# FeatherAB1805-SC.net
KiCad netlist of a schematic drawn in EAGLE
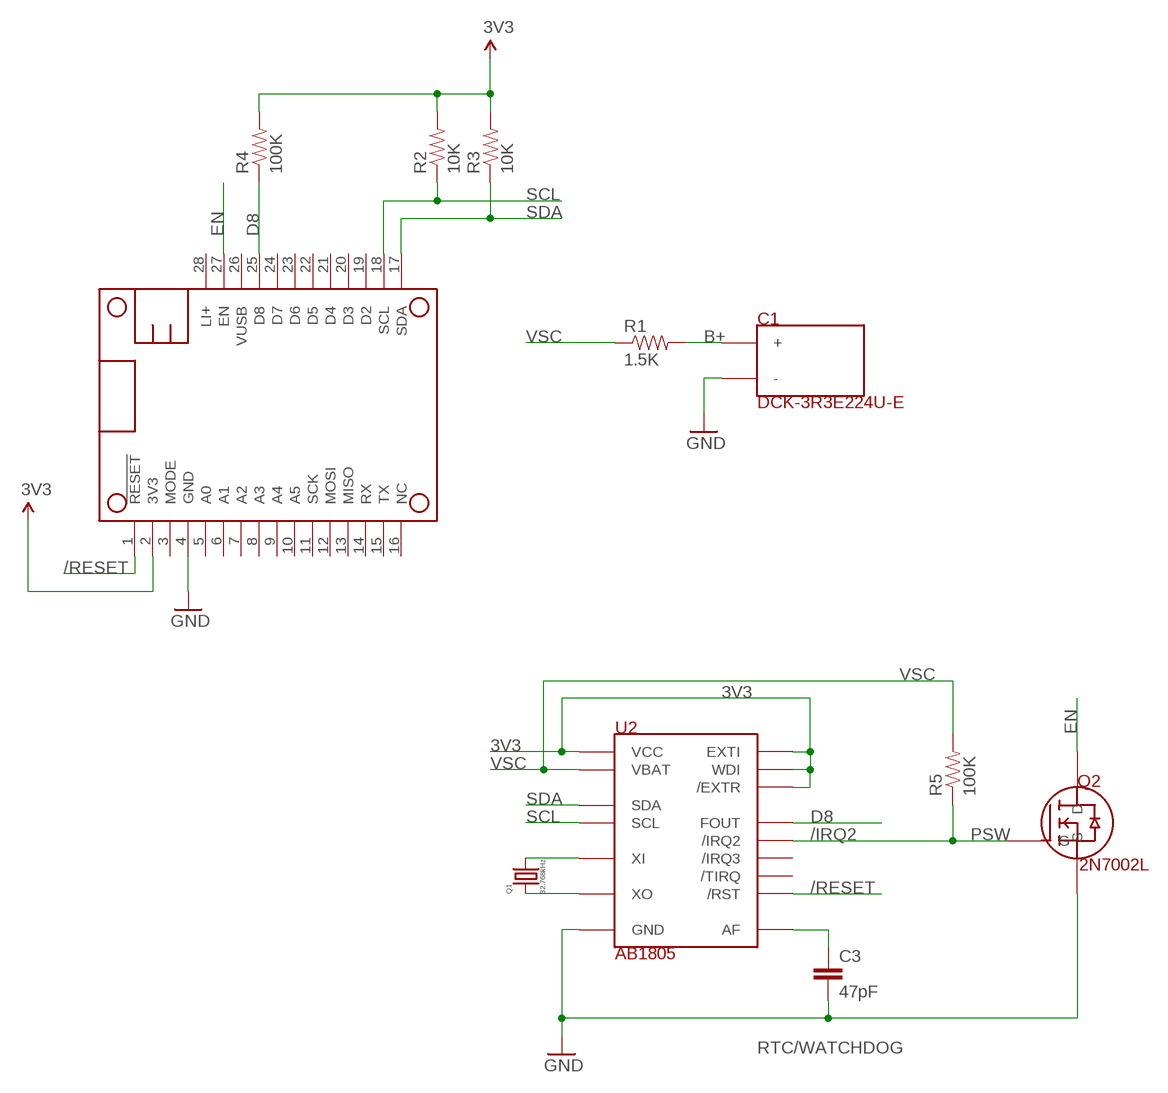
[diagram p0: schematic, sheet 1]

(export (version "E")
  (design (tool "Eeschema 10.0.6"))
  (components
    (comp (ref "C1")
      (value "DCK-3R3E224U-E")
      (footprint "eagle-import:SUPERCAP-DCK-3R3E224U-E")
      (libsource (lib "eagle-import") (part "SUPERCAP-DCK-3R3E224U-E"))
    )
    (comp (ref "C3")
      (value "47pF")
      (footprint "eagle-import:0603-CAP")
      (libsource (lib "eagle-import") (part "CAP-47PF-0603"))
    )
    (comp (ref "MS1")
      (value "FEATHERWING_NODIM")
      (footprint "eagle-import:FEATHERWING_NODIM")
      (libsource (lib "eagle-import") (part "FEATHERWING_NODIM"))
    )
    (comp (ref "Q1")
      (value "32.768kHz")
      (footprint "eagle-import:ABS07-120-CRYSTAL")
      (libsource (lib "eagle-import") (part "ABS07-120-32.768KHZ"))
    )
    (comp (ref "Q2")
      (value "2N7002L")
      (footprint "eagle-import:2N7002L")
      (libsource (lib "eagle-import") (part "2N7002L"))
    )
    (comp (ref "R1")
      (value "1.5K")
      (footprint "eagle-import:0603-RES")
      (libsource (lib "eagle-import") (part "RES-1.5K-0603"))
    )
    (comp (ref "R2")
      (value "10K")
      (footprint "eagle-import:0603-RES")
      (libsource (lib "eagle-import") (part "RES-10K-06030603"))
    )
    (comp (ref "R3")
      (value "10K")
      (footprint "eagle-import:0603-RES")
      (libsource (lib "eagle-import") (part "RES-10K-06030603"))
    )
    (comp (ref "R4")
      (value "100K")
      (footprint "eagle-import:0603-RES")
      (libsource (lib "eagle-import") (part "RES-100K-0603"))
    )
    (comp (ref "R5")
      (value "100K")
      (footprint "eagle-import:0603-RES")
      (libsource (lib "eagle-import") (part "RES-100K-0603"))
    )
    (comp (ref "U2")
      (value "AB1805")
      (footprint "eagle-import:16-VFQFN-ABRACON")
      (libsource (lib "eagle-import") (part "AB1805"))
    )
  )
  (nets
    (net (code "1") (name "/B+") (class "Default")
      (node (ref "C1") (pin "+") (pinfunction "+_+") (pintype "passive"))
      (node (ref "R1") (pin "2") (pinfunction "2_2") (pintype "passive"))
    )
    (net (code "2") (name "/D8") (class "Default")
      (node (ref "MS1") (pin "25") (pinfunction "D8_25") (pintype "bidirectional"))
      (node (ref "R4") (pin "1") (pinfunction "1_1") (pintype "passive"))
      (node (ref "U2") (pin "11") (pinfunction "FOUT_11") (pintype "output"))
    )
    (net (code "3") (name "/EN") (class "Default")
      (node (ref "MS1") (pin "27") (pinfunction "EN_27") (pintype "passive"))
      (node (ref "Q2") (pin "3") (pinfunction "D_3") (pintype "bidirectional"))
    )
    (net (code "4") (name "/LI+") (class "Default")
      (node (ref "MS1") (pin "28") (pinfunction "LI+_28") (pintype "power_in"))
    )
    (net (code "5") (name "/SCL") (class "Default")
      (node (ref "MS1") (pin "18") (pinfunction "SCL_18") (pintype "bidirectional"))
      (node (ref "R2") (pin "1") (pinfunction "1_1") (pintype "passive"))
      (node (ref "U2") (pin "7") (pinfunction "SCL_7") (pintype "bidirectional"))
    )
    (net (code "6") (name "/SDA") (class "Default")
      (node (ref "MS1") (pin "17") (pinfunction "SDA_17") (pintype "bidirectional"))
      (node (ref "R3") (pin "1") (pinfunction "1_1") (pintype "passive"))
      (node (ref "U2") (pin "6") (pinfunction "SDA_6") (pintype "bidirectional"))
    )
    (net (code "7") (name "/VSC") (class "Default")
      (node (ref "R1") (pin "1") (pinfunction "1_1") (pintype "passive"))
      (node (ref "R5") (pin "2") (pinfunction "2_2") (pintype "passive"))
      (node (ref "U2") (pin "5") (pinfunction "VBAT_5") (pintype "passive"))
    )
    (net (code "8") (name "/VUSB") (class "Default")
      (node (ref "MS1") (pin "26") (pinfunction "VUSB_26") (pintype "power_in"))
    )
    (net (code "9") (name "/{slash}IRQ2") (class "Default")
      (node (ref "Q2") (pin "1") (pinfunction "G_1") (pintype "bidirectional"))
      (node (ref "R5") (pin "1") (pinfunction "1_1") (pintype "passive"))
      (node (ref "U2") (pin "4") (pinfunction "/IRQ2_4") (pintype "output"))
    )
    (net (code "10") (name "/{slash}RESET") (class "Default")
      (node (ref "MS1") (pin "1") (pinfunction "~{RESET}_1") (pintype "input"))
      (node (ref "U2") (pin "1") (pinfunction "/RST_1") (pintype "output"))
    )
    (net (code "11") (name "3V3") (class "Default")
      (node (ref "MS1") (pin "2") (pinfunction "3V3_2") (pintype "power_in"))
      (node (ref "R2") (pin "2") (pinfunction "2_2") (pintype "passive"))
      (node (ref "R3") (pin "2") (pinfunction "2_2") (pintype "passive"))
      (node (ref "R4") (pin "2") (pinfunction "2_2") (pintype "passive"))
      (node (ref "U2") (pin "10") (pinfunction "EXTI_10") (pintype "input"))
      (node (ref "U2") (pin "13") (pinfunction "VCC_13") (pintype "passive"))
      (node (ref "U2") (pin "2") (pinfunction "WDI_2") (pintype "input"))
      (node (ref "U2") (pin "3") (pinfunction "/EXTR_3") (pintype "input"))
    )
    (net (code "12") (name "GND") (class "Default")
      (node (ref "C1") (pin "-") (pinfunction "-_-") (pintype "passive"))
      (node (ref "C3") (pin "2") (pinfunction "2_2") (pintype "passive"))
      (node (ref "MS1") (pin "4") (pinfunction "GND_4") (pintype "power_in"))
      (node (ref "Q2") (pin "2") (pinfunction "S_2") (pintype "bidirectional"))
      (node (ref "U2") (pin "9") (pinfunction "GND_9") (pintype "passive"))
      (node (ref "U2") (pin "EP") (pinfunction "GND_EP") (pintype "passive"))
    )
    (net (code "13") (name "Net-(U2-AF)") (class "Default")
      (node (ref "C3") (pin "1") (pinfunction "1_1") (pintype "passive"))
      (node (ref "U2") (pin "14") (pinfunction "AF_14") (pintype "output"))
    )
    (net (code "14") (name "Net-(U2-XI)") (class "Default")
      (node (ref "Q1") (pin "2") (pinfunction "2_2") (pintype "passive"))
      (node (ref "U2") (pin "16") (pinfunction "XI_16") (pintype "bidirectional"))
    )
    (net (code "15") (name "Net-(U2-XO)") (class "Default")
      (node (ref "Q1") (pin "1") (pinfunction "1_1") (pintype "passive"))
      (node (ref "U2") (pin "15") (pinfunction "XO_15") (pintype "bidirectional"))
    )
    (net (code "16") (name "unconnected-(MS1-A0-Pad5)") (class "Default")
      (node (ref "MS1") (pin "5") (pinfunction "A0_5") (pintype "bidirectional"))
    )
    (net (code "17") (name "unconnected-(MS1-A1-Pad6)") (class "Default")
      (node (ref "MS1") (pin "6") (pinfunction "A1_6") (pintype "bidirectional"))
    )
    (net (code "18") (name "unconnected-(MS1-A2-Pad7)") (class "Default")
      (node (ref "MS1") (pin "7") (pinfunction "A2_7") (pintype "bidirectional"))
    )
    (net (code "19") (name "unconnected-(MS1-A3-Pad8)") (class "Default")
      (node (ref "MS1") (pin "8") (pinfunction "A3_8") (pintype "bidirectional"))
    )
    (net (code "20") (name "unconnected-(MS1-A4-Pad9)") (class "Default")
      (node (ref "MS1") (pin "9") (pinfunction "A4_9") (pintype "bidirectional"))
    )
    (net (code "21") (name "unconnected-(MS1-A5-Pad10)") (class "Default")
      (node (ref "MS1") (pin "10") (pinfunction "A5_10") (pintype "bidirectional"))
    )
    (net (code "22") (name "unconnected-(MS1-D2-Pad19)") (class "Default")
      (node (ref "MS1") (pin "19") (pinfunction "D2_19") (pintype "bidirectional"))
    )
    (net (code "23") (name "unconnected-(MS1-D3-Pad20)") (class "Default")
      (node (ref "MS1") (pin "20") (pinfunction "D3_20") (pintype "bidirectional"))
    )
    (net (code "24") (name "unconnected-(MS1-D4-Pad21)") (class "Default")
      (node (ref "MS1") (pin "21") (pinfunction "D4_21") (pintype "bidirectional"))
    )
    (net (code "25") (name "unconnected-(MS1-D5-Pad22)") (class "Default")
      (node (ref "MS1") (pin "22") (pinfunction "D5_22") (pintype "bidirectional"))
    )
    (net (code "26") (name "unconnected-(MS1-D6-Pad23)") (class "Default")
      (node (ref "MS1") (pin "23") (pinfunction "D6_23") (pintype "bidirectional"))
    )
    (net (code "27") (name "unconnected-(MS1-D7-Pad24)") (class "Default")
      (node (ref "MS1") (pin "24") (pinfunction "D7_24") (pintype "bidirectional"))
    )
    (net (code "28") (name "unconnected-(MS1-MISO-Pad13)") (class "Default")
      (node (ref "MS1") (pin "13") (pinfunction "MISO_13") (pintype "bidirectional"))
    )
    (net (code "29") (name "unconnected-(MS1-MODE-Pad3)") (class "Default")
      (node (ref "MS1") (pin "3") (pinfunction "MODE_3") (pintype "passive"))
    )
    (net (code "30") (name "unconnected-(MS1-MOSI-Pad12)") (class "Default")
      (node (ref "MS1") (pin "12") (pinfunction "MOSI_12") (pintype "bidirectional"))
    )
    (net (code "31") (name "unconnected-(MS1-NC-Pad16)") (class "Default")
      (node (ref "MS1") (pin "16") (pinfunction "NC_16") (pintype "passive"))
    )
    (net (code "32") (name "unconnected-(MS1-RX-Pad14)") (class "Default")
      (node (ref "MS1") (pin "14") (pinfunction "RX_14") (pintype "bidirectional"))
    )
    (net (code "33") (name "unconnected-(MS1-SCK-Pad11)") (class "Default")
      (node (ref "MS1") (pin "11") (pinfunction "SCK_11") (pintype "bidirectional"))
    )
    (net (code "34") (name "unconnected-(MS1-TX-Pad15)") (class "Default")
      (node (ref "MS1") (pin "15") (pinfunction "TX_15") (pintype "bidirectional"))
    )
    (net (code "35") (name "unconnected-(U2-{slash}IRQ3-Pad8)") (class "Default")
      (node (ref "U2") (pin "8") (pinfunction "/IRQ3_8") (pintype "output"))
    )
    (net (code "36") (name "unconnected-(U2-{slash}TIRQ-Pad12)") (class "Default")
      (node (ref "U2") (pin "12") (pinfunction "/TIRQ_12") (pintype "output"))
    )
  )
)
